# InverterSmd.net
KiCad netlist of a schematic drawn in EAGLE
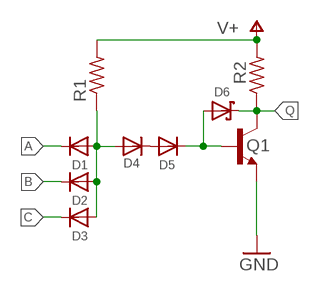
[diagram p0: schematic, sheet 1]

(export (version "E")
  (design (tool "Eeschema 10.0.6"))
  (components
    (comp (ref "D1")
      (value "DIODE-SOD323")
      (footprint "eagle-import:SOD323F")
      (libsource (lib "eagle-import") (part "DIODE-SOD323"))
    )
    (comp (ref "D2")
      (value "DIODE-SOD323")
      (footprint "eagle-import:SOD323F")
      (libsource (lib "eagle-import") (part "DIODE-SOD323"))
    )
    (comp (ref "D3")
      (value "DIODE-SOD323")
      (footprint "eagle-import:SOD323F")
      (libsource (lib "eagle-import") (part "DIODE-SOD323"))
    )
    (comp (ref "D4")
      (value "DIODE-SOD323")
      (footprint "eagle-import:SOD323F")
      (libsource (lib "eagle-import") (part "DIODE-SOD323"))
    )
    (comp (ref "D5")
      (value "DIODE-SOD323")
      (footprint "eagle-import:SOD323F")
      (libsource (lib "eagle-import") (part "DIODE-SOD323"))
    )
    (comp (ref "D6")
      (value "SCHOTTKYSOT323")
      (footprint "eagle-import:SOT23")
      (libsource (lib "eagle-import") (part "SCHOTTKYSOT323"))
    )
    (comp (ref "Q1")
      (value "BC547-SOT23")
      (footprint "eagle-import:SOT23")
      (libsource (lib "eagle-import") (part "BC547-SOT23"))
    )
    (comp (ref "R1")
      (value "470")
      (footprint "eagle-import:R0805")
      (libsource (lib "eagle-import") (part "R-0805"))
    )
    (comp (ref "R2")
      (value "150")
      (footprint "eagle-import:R0805")
      (libsource (lib "eagle-import") (part "R-0805"))
    )
  )
  (nets
    (net (code "1") (name "A") (class "Default")
      (node (ref "D1") (pin "C") (pinfunction "C_C") (pintype "passive"))
    )
    (net (code "2") (name "B") (class "Default")
      (node (ref "D2") (pin "C") (pinfunction "C_C") (pintype "passive"))
    )
    (net (code "3") (name "C") (class "Default")
      (node (ref "D3") (pin "C") (pinfunction "C_C") (pintype "passive"))
    )
    (net (code "4") (name "GND") (class "Default")
      (node (ref "Q1") (pin "2") (pinfunction "E_2") (pintype "passive"))
    )
    (net (code "5") (name "Net-(D1-PadA)") (class "Default")
      (node (ref "D1") (pin "A") (pinfunction "A_A") (pintype "passive"))
      (node (ref "D2") (pin "A") (pinfunction "A_A") (pintype "passive"))
      (node (ref "D3") (pin "A") (pinfunction "A_A") (pintype "passive"))
      (node (ref "D4") (pin "A") (pinfunction "A_A") (pintype "passive"))
      (node (ref "R1") (pin "1") (pinfunction "1_1") (pintype "passive"))
    )
    (net (code "6") (name "Net-(D4-PadC)") (class "Default")
      (node (ref "D4") (pin "C") (pinfunction "C_C") (pintype "passive"))
      (node (ref "D5") (pin "A") (pinfunction "A_A") (pintype "passive"))
    )
    (net (code "7") (name "Net-(D6-A)") (class "Default")
      (node (ref "D5") (pin "C") (pinfunction "C_C") (pintype "passive"))
      (node (ref "D6") (pin "1") (pinfunction "A_1") (pintype "passive"))
      (node (ref "Q1") (pin "1") (pinfunction "B_1") (pintype "passive"))
    )
    (net (code "8") (name "Q") (class "Default")
      (node (ref "D6") (pin "3") (pinfunction "C_3") (pintype "passive"))
      (node (ref "Q1") (pin "3") (pinfunction "C_3") (pintype "passive"))
      (node (ref "R2") (pin "1") (pinfunction "1_1") (pintype "passive"))
    )
    (net (code "9") (name "V+") (class "Default")
      (node (ref "R1") (pin "2") (pinfunction "2_2") (pintype "passive"))
      (node (ref "R2") (pin "2") (pinfunction "2_2") (pintype "passive"))
    )
  )
)
